# HeadsetR2.net
KiCad netlist of a schematic drawn in EAGLE
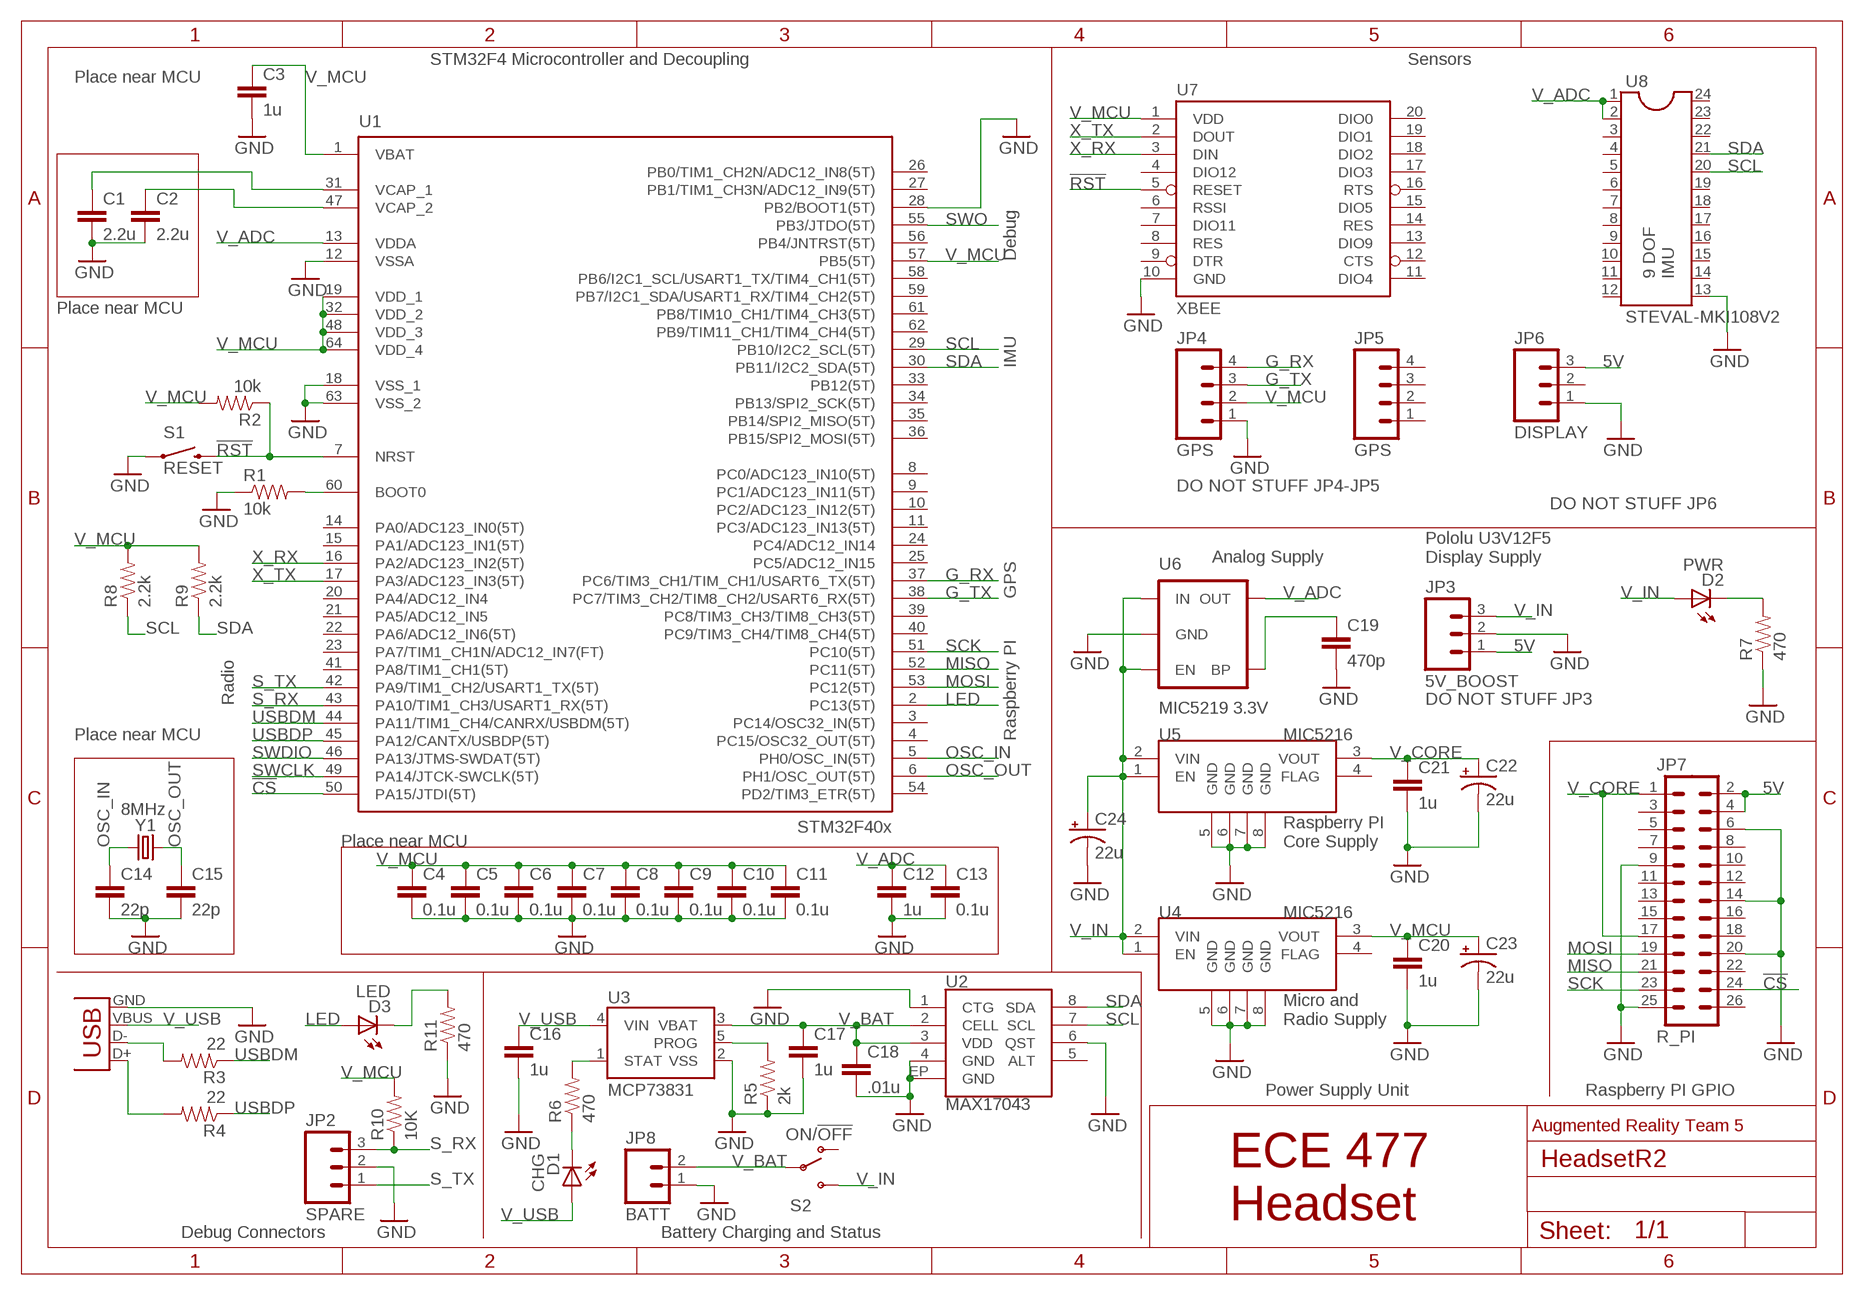
[diagram p0: schematic, sheet 1]

(export (version "E")
  (design (tool "Eeschema 10.0.6"))
  (components
    (comp (ref "C1")
      (value "2.2u")
      (footprint "eagle-import:1206")
      (libsource (lib "eagle-import") (part "CAP1206"))
    )
    (comp (ref "C2")
      (value "2.2u")
      (footprint "eagle-import:1206")
      (libsource (lib "eagle-import") (part "CAP1206"))
    )
    (comp (ref "C3")
      (value "1u")
      (footprint "eagle-import:1206")
      (libsource (lib "eagle-import") (part "CAP1206"))
    )
    (comp (ref "C4")
      (value "0.1u")
      (footprint "eagle-import:1206")
      (libsource (lib "eagle-import") (part "CAP1206"))
    )
    (comp (ref "C5")
      (value "0.1u")
      (footprint "eagle-import:1206")
      (libsource (lib "eagle-import") (part "CAP1206"))
    )
    (comp (ref "C6")
      (value "0.1u")
      (footprint "eagle-import:1206")
      (libsource (lib "eagle-import") (part "CAP1206"))
    )
    (comp (ref "C7")
      (value "0.1u")
      (footprint "eagle-import:1206")
      (libsource (lib "eagle-import") (part "CAP1206"))
    )
    (comp (ref "C8")
      (value "0.1u")
      (footprint "eagle-import:1206")
      (libsource (lib "eagle-import") (part "CAP1206"))
    )
    (comp (ref "C9")
      (value "0.1u")
      (footprint "eagle-import:1206")
      (libsource (lib "eagle-import") (part "CAP1206"))
    )
    (comp (ref "C10")
      (value "0.1u")
      (footprint "eagle-import:1206")
      (libsource (lib "eagle-import") (part "CAP1206"))
    )
    (comp (ref "C11")
      (value "0.1u")
      (footprint "eagle-import:1206")
      (libsource (lib "eagle-import") (part "CAP1206"))
    )
    (comp (ref "C12")
      (value "1u")
      (footprint "eagle-import:1206")
      (libsource (lib "eagle-import") (part "CAP1206"))
    )
    (comp (ref "C13")
      (value "0.1u")
      (footprint "eagle-import:1206")
      (libsource (lib "eagle-import") (part "CAP1206"))
    )
    (comp (ref "C14")
      (value "22p")
      (footprint "eagle-import:1206")
      (libsource (lib "eagle-import") (part "CAP1206"))
    )
    (comp (ref "C15")
      (value "22p")
      (footprint "eagle-import:1206")
      (libsource (lib "eagle-import") (part "CAP1206"))
    )
    (comp (ref "C16")
      (value "1u")
      (footprint "eagle-import:1206")
      (libsource (lib "eagle-import") (part "CAP1206"))
    )
    (comp (ref "C17")
      (value "1u")
      (footprint "eagle-import:1206")
      (libsource (lib "eagle-import") (part "CAP1206"))
    )
    (comp (ref "C18")
      (value ".01u")
      (footprint "eagle-import:1206")
      (libsource (lib "eagle-import") (part "CAP1206"))
    )
    (comp (ref "C19")
      (value "470p")
      (footprint "eagle-import:1206")
      (libsource (lib "eagle-import") (part "CAP1206"))
    )
    (comp (ref "C20")
      (value "1u")
      (footprint "eagle-import:1206")
      (libsource (lib "eagle-import") (part "CAP1206"))
    )
    (comp (ref "C21")
      (value "1u")
      (footprint "eagle-import:1206")
      (libsource (lib "eagle-import") (part "CAP1206"))
    )
    (comp (ref "C22")
      (value "22u")
      (footprint "eagle-import:PANASONIC_D")
      (libsource (lib "eagle-import") (part "CAP_POLD"))
    )
    (comp (ref "C23")
      (value "22u")
      (footprint "eagle-import:PANASONIC_D")
      (libsource (lib "eagle-import") (part "CAP_POLD"))
    )
    (comp (ref "C24")
      (value "22u")
      (footprint "eagle-import:PANASONIC_D")
      (libsource (lib "eagle-import") (part "CAP_POLD"))
    )
    (comp (ref "D1")
      (value "CHG")
      (footprint "eagle-import:LED-1206")
      (libsource (lib "eagle-import") (part "LED-RED1206"))
    )
    (comp (ref "D2")
      (value "PWR")
      (footprint "eagle-import:LED-1206")
      (libsource (lib "eagle-import") (part "LED-RED1206"))
    )
    (comp (ref "D3")
      (value "LED")
      (footprint "eagle-import:LED-1206")
      (libsource (lib "eagle-import") (part "LED-RED1206"))
    )
    (comp (ref "JP1")
      (value "USBSMD")
      (footprint "eagle-import:USB-MINIB")
      (libsource (lib "eagle-import") (part "USBSMD"))
    )
    (comp (ref "JP2")
      (value "SPARE")
      (footprint "eagle-import:1X03")
      (libsource (lib "eagle-import") (part "M03PTH"))
    )
    (comp (ref "JP3")
      (value "5V_BOOST")
      (footprint "eagle-import:1X03")
      (libsource (lib "eagle-import") (part "M03PTH"))
    )
    (comp (ref "JP4")
      (value "GPS")
      (footprint "eagle-import:1X04")
      (libsource (lib "eagle-import") (part "M04PTH"))
    )
    (comp (ref "JP5")
      (value "GPS")
      (footprint "eagle-import:1X04")
      (libsource (lib "eagle-import") (part "M04PTH"))
    )
    (comp (ref "JP6")
      (value "DISPLAY")
      (footprint "eagle-import:1X03")
      (libsource (lib "eagle-import") (part "M03PTH"))
    )
    (comp (ref "JP7")
      (value "R_PI")
      (footprint "eagle-import:2X13")
      (libsource (lib "eagle-import") (part "M13X22X13"))
    )
    (comp (ref "JP8")
      (value "BATT")
      (footprint "eagle-import:JST-2-PTH")
      (libsource (lib "eagle-import") (part "M02JST-PTH-2"))
    )
    (comp (ref "R1")
      (value "10k")
      (footprint "eagle-import:1206")
      (libsource (lib "eagle-import") (part "RES1206"))
    )
    (comp (ref "R2")
      (value "10k")
      (footprint "eagle-import:1206")
      (libsource (lib "eagle-import") (part "RES1206"))
    )
    (comp (ref "R3")
      (value "22")
      (footprint "eagle-import:1206")
      (libsource (lib "eagle-import") (part "RES1206"))
    )
    (comp (ref "R4")
      (value "22")
      (footprint "eagle-import:1206")
      (libsource (lib "eagle-import") (part "RES1206"))
    )
    (comp (ref "R5")
      (value "2k")
      (footprint "eagle-import:1206")
      (libsource (lib "eagle-import") (part "RES1206"))
    )
    (comp (ref "R6")
      (value "470")
      (footprint "eagle-import:1206")
      (libsource (lib "eagle-import") (part "RES1206"))
    )
    (comp (ref "R7")
      (value "470")
      (footprint "eagle-import:1206")
      (libsource (lib "eagle-import") (part "RES1206"))
    )
    (comp (ref "R8")
      (value "2.2k")
      (footprint "eagle-import:1206")
      (libsource (lib "eagle-import") (part "RES1206"))
    )
    (comp (ref "R9")
      (value "2.2k")
      (footprint "eagle-import:1206")
      (libsource (lib "eagle-import") (part "RES1206"))
    )
    (comp (ref "R10")
      (value "10K")
      (footprint "eagle-import:1206")
      (libsource (lib "eagle-import") (part "RES1206"))
    )
    (comp (ref "R11")
      (value "470")
      (footprint "eagle-import:1206")
      (libsource (lib "eagle-import") (part "RES1206"))
    )
    (comp (ref "S1")
      (value "RESET")
      (footprint "eagle-import:TACTILE-PTH")
      (libsource (lib "eagle-import") (part "SWITCH-MOMENTARY-2PTH"))
    )
    (comp (ref "S2")
      (value "ON/!OFF!")
      (footprint "eagle-import:SWITCH-SPDT")
      (libsource (lib "eagle-import") (part "SWITCH-SPDTPTH"))
    )
    (comp (ref "U1")
      (value "STM32F405RGT6")
      (footprint "eagle-import:TQFP64")
      (libsource (lib "eagle-import") (part "STM32F405R"))
    )
    (comp (ref "U2")
      (value "MAX17043")
      (footprint "eagle-import:TDFN-8")
      (libsource (lib "eagle-import") (part "MAX1704X"))
    )
    (comp (ref "U3")
      (value "MCP73831")
      (footprint "eagle-import:SOT23-5")
      (libsource (lib "eagle-import") (part "MCP73831"))
    )
    (comp (ref "U4")
      (value "MIC5216")
      (footprint "eagle-import:MSOP8")
      (libsource (lib "eagle-import") (part "V_REG_MIC5216"))
    )
    (comp (ref "U5")
      (value "MIC5216")
      (footprint "eagle-import:MSOP8")
      (libsource (lib "eagle-import") (part "V_REG_MIC5216"))
    )
    (comp (ref "U6")
      (value "MIC5219 3.3V")
      (footprint "eagle-import:SOT23-5")
      (libsource (lib "eagle-import") (part "V_REG_MIC52193.3V"))
    )
    (comp (ref "U7")
      (value "XBEE")
      (footprint "eagle-import:XBEE-1")
      (libsource (lib "eagle-import") (part "XBEE-1B1"))
    )
    (comp (ref "U8")
      (value "STEVAL-MKI108V2")
      (footprint "eagle-import:DIL24-6")
      (libsource (lib "eagle-import") (part "DIL24-6"))
    )
    (comp (ref "Y1")
      (value "8MHz")
      (footprint "eagle-import:HC49UP")
      (libsource (lib "eagle-import") (part "CRYSTALSMD"))
    )
  )
  (nets
    (net (code "1") (name "/5V") (class "Default")
      (node (ref "JP3") (pin "1") (pinfunction "1_1") (pintype "passive"))
      (node (ref "JP6") (pin "3") (pinfunction "3_3") (pintype "passive"))
      (node (ref "JP7") (pin "2") (pinfunction "2_2") (pintype "passive"))
      (node (ref "JP7") (pin "4") (pinfunction "4_4") (pintype "passive"))
    )
    (net (code "2") (name "/G_RX") (class "Default")
      (node (ref "JP4") (pin "4") (pinfunction "4_4") (pintype "passive"))
      (node (ref "U1") (pin "37") (pinfunction "PC6/TIM3_CH1/TIM_CH1/USART6_TX(5T)_37") (pintype "bidirectional"))
    )
    (net (code "3") (name "/G_TX") (class "Default")
      (node (ref "JP4") (pin "3") (pinfunction "3_3") (pintype "passive"))
      (node (ref "U1") (pin "38") (pinfunction "PC7/TIM3_CH2/TIM8_CH2/USART6_RX(5T)_38") (pintype "bidirectional"))
    )
    (net (code "4") (name "/LED") (class "Default")
      (node (ref "D3") (pin "A") (pinfunction "A_A") (pintype "passive"))
      (node (ref "U1") (pin "2") (pinfunction "PC13(5T)_2") (pintype "bidirectional"))
    )
    (net (code "5") (name "/MISO") (class "Default")
      (node (ref "JP7") (pin "21") (pinfunction "21_21") (pintype "passive"))
      (node (ref "U1") (pin "52") (pinfunction "PC11(5T)_52") (pintype "bidirectional"))
    )
    (net (code "6") (name "/MOSI") (class "Default")
      (node (ref "JP7") (pin "19") (pinfunction "19_19") (pintype "passive"))
      (node (ref "U1") (pin "53") (pinfunction "PC12(5T)_53") (pintype "bidirectional"))
    )
    (net (code "7") (name "/OSC_IN") (class "Default")
      (node (ref "C14") (pin "1") (pinfunction "1_1") (pintype "passive"))
      (node (ref "U1") (pin "5") (pinfunction "PH0/OSC_IN(5T)_5") (pintype "bidirectional"))
      (node (ref "Y1") (pin "1") (pinfunction "1_1") (pintype "passive"))
    )
    (net (code "8") (name "/OSC_OUT") (class "Default")
      (node (ref "C15") (pin "1") (pinfunction "1_1") (pintype "passive"))
      (node (ref "U1") (pin "6") (pinfunction "PH1/OSC_OUT(5T)_6") (pintype "bidirectional"))
      (node (ref "Y1") (pin "2") (pinfunction "2_2") (pintype "passive"))
    )
    (net (code "9") (name "/SCK") (class "Default")
      (node (ref "JP7") (pin "23") (pinfunction "23_23") (pintype "passive"))
      (node (ref "U1") (pin "51") (pinfunction "PC10(5T)_51") (pintype "bidirectional"))
    )
    (net (code "10") (name "/SCL") (class "Default")
      (node (ref "R8") (pin "1") (pinfunction "1_1") (pintype "passive"))
      (node (ref "U1") (pin "29") (pinfunction "PB10/I2C2_SCL(5T)_29") (pintype "bidirectional"))
      (node (ref "U2") (pin "7") (pinfunction "SCL_7") (pintype "bidirectional"))
      (node (ref "U8") (pin "20") (pinfunction "20_20") (pintype "passive"))
    )
    (net (code "11") (name "/SDA") (class "Default")
      (node (ref "R9") (pin "1") (pinfunction "1_1") (pintype "passive"))
      (node (ref "U1") (pin "30") (pinfunction "PB11/I2C2_SDA(5T)_30") (pintype "bidirectional"))
      (node (ref "U2") (pin "8") (pinfunction "SDA_8") (pintype "bidirectional"))
      (node (ref "U8") (pin "21") (pinfunction "21_21") (pintype "passive"))
    )
    (net (code "12") (name "/SWCLK") (class "Default")
      (node (ref "U1") (pin "49") (pinfunction "PA14/JTCK-SWCLK(5T)_49") (pintype "bidirectional"))
    )
    (net (code "13") (name "/SWDIO") (class "Default")
      (node (ref "U1") (pin "46") (pinfunction "PA13/JTMS-SWDAT(5T)_46") (pintype "bidirectional"))
    )
    (net (code "14") (name "/SWO") (class "Default")
      (node (ref "U1") (pin "55") (pinfunction "PB3/JTDO(5T)_55") (pintype "bidirectional"))
    )
    (net (code "15") (name "/S_RX") (class "Default")
      (node (ref "JP2") (pin "3") (pinfunction "3_3") (pintype "passive"))
      (node (ref "R10") (pin "1") (pinfunction "1_1") (pintype "passive"))
      (node (ref "U1") (pin "43") (pinfunction "PA10/TIM1_CH3/USART1_RX(5T)_43") (pintype "bidirectional"))
    )
    (net (code "16") (name "/S_TX") (class "Default")
      (node (ref "JP2") (pin "1") (pinfunction "1_1") (pintype "passive"))
      (node (ref "U1") (pin "42") (pinfunction "PA9/TIM1_CH2/USART1_TX(5T)_42") (pintype "bidirectional"))
    )
    (net (code "17") (name "/USBDM") (class "Default")
      (node (ref "R3") (pin "1") (pinfunction "1_1") (pintype "passive"))
      (node (ref "U1") (pin "44") (pinfunction "PA11/TIM1_CH4/CANRX/USBDM(5T)_44") (pintype "bidirectional"))
    )
    (net (code "18") (name "/USBDP") (class "Default")
      (node (ref "R4") (pin "1") (pinfunction "1_1") (pintype "passive"))
      (node (ref "U1") (pin "45") (pinfunction "PA12/CANTX/USBDP(5T)_45") (pintype "bidirectional"))
    )
    (net (code "19") (name "/V_ADC") (class "Default")
      (node (ref "C12") (pin "1") (pinfunction "1_1") (pintype "passive"))
      (node (ref "C13") (pin "1") (pinfunction "1_1") (pintype "passive"))
      (node (ref "U1") (pin "13") (pinfunction "VDDA_13") (pintype "bidirectional"))
      (node (ref "U6") (pin "5") (pinfunction "OUT_5") (pintype "passive"))
      (node (ref "U8") (pin "1") (pinfunction "1_1") (pintype "passive"))
      (node (ref "U8") (pin "2") (pinfunction "2_2") (pintype "passive"))
    )
    (net (code "20") (name "/V_BAT") (class "Default")
      (node (ref "C17") (pin "1") (pinfunction "1_1") (pintype "passive"))
      (node (ref "C18") (pin "1") (pinfunction "1_1") (pintype "passive"))
      (node (ref "JP8") (pin "2") (pinfunction "2_2") (pintype "passive"))
      (node (ref "S2") (pin "2") (pinfunction "P_2") (pintype "passive"))
      (node (ref "U2") (pin "2") (pinfunction "CELL_2") (pintype "bidirectional"))
      (node (ref "U2") (pin "3") (pinfunction "VDD_3") (pintype "bidirectional"))
      (node (ref "U3") (pin "3") (pinfunction "VBAT_3") (pintype "power_in"))
    )
    (net (code "21") (name "/V_CORE") (class "Default")
      (node (ref "C21") (pin "1") (pinfunction "1_1") (pintype "passive"))
      (node (ref "C22") (pin "+") (pinfunction "+_+") (pintype "passive"))
      (node (ref "JP7") (pin "1") (pinfunction "1_1") (pintype "passive"))
      (node (ref "JP7") (pin "17") (pinfunction "17_17") (pintype "passive"))
      (node (ref "U5") (pin "3") (pinfunction "VOUT_3") (pintype "bidirectional"))
    )
    (net (code "22") (name "/V_IN") (class "Default")
      (node (ref "C24") (pin "+") (pinfunction "+_+") (pintype "passive"))
      (node (ref "D2") (pin "A") (pinfunction "A_A") (pintype "passive"))
      (node (ref "JP3") (pin "3") (pinfunction "3_3") (pintype "passive"))
      (node (ref "S2") (pin "3") (pinfunction "S_3") (pintype "passive"))
      (node (ref "U4") (pin "1") (pinfunction "EN_1") (pintype "bidirectional"))
      (node (ref "U4") (pin "2") (pinfunction "VIN_2") (pintype "bidirectional"))
      (node (ref "U5") (pin "1") (pinfunction "EN_1") (pintype "bidirectional"))
      (node (ref "U5") (pin "2") (pinfunction "VIN_2") (pintype "bidirectional"))
      (node (ref "U6") (pin "1") (pinfunction "IN_1") (pintype "input"))
      (node (ref "U6") (pin "3") (pinfunction "EN_3") (pintype "input"))
    )
    (net (code "23") (name "/V_MCU") (class "Default")
      (node (ref "C10") (pin "1") (pinfunction "1_1") (pintype "passive"))
      (node (ref "C11") (pin "1") (pinfunction "1_1") (pintype "passive"))
      (node (ref "C20") (pin "1") (pinfunction "1_1") (pintype "passive"))
      (node (ref "C23") (pin "+") (pinfunction "+_+") (pintype "passive"))
      (node (ref "C3") (pin "1") (pinfunction "1_1") (pintype "passive"))
      (node (ref "C4") (pin "1") (pinfunction "1_1") (pintype "passive"))
      (node (ref "C5") (pin "1") (pinfunction "1_1") (pintype "passive"))
      (node (ref "C6") (pin "1") (pinfunction "1_1") (pintype "passive"))
      (node (ref "C7") (pin "1") (pinfunction "1_1") (pintype "passive"))
      (node (ref "C8") (pin "1") (pinfunction "1_1") (pintype "passive"))
      (node (ref "C9") (pin "1") (pinfunction "1_1") (pintype "passive"))
      (node (ref "JP4") (pin "2") (pinfunction "2_2") (pintype "passive"))
      (node (ref "R10") (pin "2") (pinfunction "2_2") (pintype "passive"))
      (node (ref "R2") (pin "2") (pinfunction "2_2") (pintype "passive"))
      (node (ref "R8") (pin "2") (pinfunction "2_2") (pintype "passive"))
      (node (ref "R9") (pin "2") (pinfunction "2_2") (pintype "passive"))
      (node (ref "U1") (pin "1") (pinfunction "VBAT_1") (pintype "bidirectional"))
      (node (ref "U1") (pin "19") (pinfunction "VDD_1_19") (pintype "bidirectional"))
      (node (ref "U1") (pin "32") (pinfunction "VDD_2_32") (pintype "bidirectional"))
      (node (ref "U1") (pin "48") (pinfunction "VDD_3_48") (pintype "bidirectional"))
      (node (ref "U1") (pin "57") (pinfunction "PB5(5T)_57") (pintype "bidirectional"))
      (node (ref "U1") (pin "64") (pinfunction "VDD_4_64") (pintype "bidirectional"))
      (node (ref "U4") (pin "3") (pinfunction "VOUT_3") (pintype "bidirectional"))
      (node (ref "U7") (pin "1") (pinfunction "VDD_1") (pintype "power_in"))
    )
    (net (code "24") (name "/V_USB") (class "Default")
      (node (ref "C16") (pin "1") (pinfunction "1_1") (pintype "passive"))
      (node (ref "D1") (pin "A") (pinfunction "A_A") (pintype "passive"))
      (node (ref "JP1") (pin "VBUS") (pinfunction "VBUS_VBUS") (pintype "bidirectional"))
      (node (ref "U3") (pin "4") (pinfunction "VIN_4") (pintype "power_in"))
    )
    (net (code "25") (name "/X_RX") (class "Default")
      (node (ref "U1") (pin "16") (pinfunction "PA2/ADC123_IN2(5T)_16") (pintype "bidirectional"))
      (node (ref "U7") (pin "3") (pinfunction "DIN_3") (pintype "input"))
    )
    (net (code "26") (name "/X_TX") (class "Default")
      (node (ref "U1") (pin "17") (pinfunction "PA3/ADC123_IN3(5T)_17") (pintype "bidirectional"))
      (node (ref "U7") (pin "2") (pinfunction "DOUT_2") (pintype "output"))
    )
    (net (code "27") (name "/~{CS}") (class "Default")
      (node (ref "JP7") (pin "24") (pinfunction "24_24") (pintype "passive"))
      (node (ref "U1") (pin "50") (pinfunction "PA15/JTDI(5T)_50") (pintype "bidirectional"))
    )
    (net (code "28") (name "/~{RST}") (class "Default")
      (node (ref "R2") (pin "1") (pinfunction "1_1") (pintype "passive"))
      (node (ref "S1") (pin "3") (pinfunction "2_3") (pintype "passive"))
      (node (ref "U1") (pin "7") (pinfunction "NRST_7") (pintype "bidirectional"))
      (node (ref "U7") (pin "5") (pinfunction "RESET_5") (pintype "input"))
    )
    (net (code "29") (name "GND") (class "Default")
      (node (ref "C1") (pin "2") (pinfunction "2_2") (pintype "passive"))
      (node (ref "C10") (pin "2") (pinfunction "2_2") (pintype "passive"))
      (node (ref "C11") (pin "2") (pinfunction "2_2") (pintype "passive"))
      (node (ref "C12") (pin "2") (pinfunction "2_2") (pintype "passive"))
      (node (ref "C13") (pin "2") (pinfunction "2_2") (pintype "passive"))
      (node (ref "C14") (pin "2") (pinfunction "2_2") (pintype "passive"))
      (node (ref "C15") (pin "2") (pinfunction "2_2") (pintype "passive"))
      (node (ref "C16") (pin "2") (pinfunction "2_2") (pintype "passive"))
      (node (ref "C17") (pin "2") (pinfunction "2_2") (pintype "passive"))
      (node (ref "C18") (pin "2") (pinfunction "2_2") (pintype "passive"))
      (node (ref "C19") (pin "2") (pinfunction "2_2") (pintype "passive"))
      (node (ref "C2") (pin "2") (pinfunction "2_2") (pintype "passive"))
      (node (ref "C20") (pin "2") (pinfunction "2_2") (pintype "passive"))
      (node (ref "C21") (pin "2") (pinfunction "2_2") (pintype "passive"))
      (node (ref "C22") (pin "-") (pinfunction "-_-") (pintype "passive"))
      (node (ref "C23") (pin "-") (pinfunction "-_-") (pintype "passive"))
      (node (ref "C24") (pin "-") (pinfunction "-_-") (pintype "passive"))
      (node (ref "C3") (pin "2") (pinfunction "2_2") (pintype "passive"))
      (node (ref "C4") (pin "2") (pinfunction "2_2") (pintype "passive"))
      (node (ref "C5") (pin "2") (pinfunction "2_2") (pintype "passive"))
      (node (ref "C6") (pin "2") (pinfunction "2_2") (pintype "passive"))
      (node (ref "C7") (pin "2") (pinfunction "2_2") (pintype "passive"))
      (node (ref "C8") (pin "2") (pinfunction "2_2") (pintype "passive"))
      (node (ref "C9") (pin "2") (pinfunction "2_2") (pintype "passive"))
      (node (ref "JP1") (pin "GND") (pinfunction "GND_GND") (pintype "bidirectional"))
      (node (ref "JP2") (pin "2") (pinfunction "2_2") (pintype "passive"))
      (node (ref "JP3") (pin "2") (pinfunction "2_2") (pintype "passive"))
      (node (ref "JP4") (pin "1") (pinfunction "1_1") (pintype "passive"))
      (node (ref "JP6") (pin "1") (pinfunction "1_1") (pintype "passive"))
      (node (ref "JP7") (pin "14") (pinfunction "14_14") (pintype "passive"))
      (node (ref "JP7") (pin "20") (pinfunction "20_20") (pintype "passive"))
      (node (ref "JP7") (pin "25") (pinfunction "25_25") (pintype "passive"))
      (node (ref "JP7") (pin "6") (pinfunction "6_6") (pintype "passive"))
      (node (ref "JP7") (pin "9") (pinfunction "9_9") (pintype "passive"))
      (node (ref "JP8") (pin "1") (pinfunction "1_1") (pintype "passive"))
      (node (ref "R1") (pin "1") (pinfunction "1_1") (pintype "passive"))
      (node (ref "R11") (pin "1") (pinfunction "1_1") (pintype "passive"))
      (node (ref "R5") (pin "1") (pinfunction "1_1") (pintype "passive"))
      (node (ref "R7") (pin "1") (pinfunction "1_1") (pintype "passive"))
      (node (ref "S1") (pin "1") (pinfunction "1_1") (pintype "passive"))
      (node (ref "U1") (pin "12") (pinfunction "VSSA_12") (pintype "bidirectional"))
      (node (ref "U1") (pin "18") (pinfunction "VSS_1_18") (pintype "bidirectional"))
      (node (ref "U1") (pin "28") (pinfunction "PB2/BOOT1(5T)_28") (pintype "bidirectional"))
      (node (ref "U1") (pin "63") (pinfunction "VSS_2_63") (pintype "bidirectional"))
      (node (ref "U2") (pin "1") (pinfunction "CTG_1") (pintype "bidirectional"))
      (node (ref "U2") (pin "4") (pinfunction "GND_4") (pintype "bidirectional"))
      (node (ref "U2") (pin "6") (pinfunction "QST_6") (pintype "bidirectional"))
      (node (ref "U2") (pin "EP") (pinfunction "GND_EP") (pintype "bidirectional"))
      (node (ref "U3") (pin "2") (pinfunction "VSS_2") (pintype "power_in"))
      (node (ref "U4") (pin "5") (pinfunction "GND_5") (pintype "bidirectional"))
      (node (ref "U4") (pin "6") (pinfunction "GND_6") (pintype "bidirectional"))
      (node (ref "U4") (pin "7") (pinfunction "GND_7") (pintype "bidirectional"))
      (node (ref "U4") (pin "8") (pinfunction "GND_8") (pintype "bidirectional"))
      (node (ref "U5") (pin "5") (pinfunction "GND_5") (pintype "bidirectional"))
      (node (ref "U5") (pin "6") (pinfunction "GND_6") (pintype "bidirectional"))
      (node (ref "U5") (pin "7") (pinfunction "GND_7") (pintype "bidirectional"))
      (node (ref "U5") (pin "8") (pinfunction "GND_8") (pintype "bidirectional"))
      (node (ref "U6") (pin "2") (pinfunction "GND_2") (pintype "input"))
      (node (ref "U7") (pin "10") (pinfunction "GND_10") (pintype "power_in"))
      (node (ref "U8") (pin "13") (pinfunction "13_13") (pintype "passive"))
    )
    (net (code "30") (name "Net-(D1-PadC)") (class "Default")
      (node (ref "D1") (pin "C") (pinfunction "C_C") (pintype "passive"))
      (node (ref "R6") (pin "1") (pinfunction "1_1") (pintype "passive"))
    )
    (net (code "31") (name "Net-(D2-PadC)") (class "Default")
      (node (ref "D2") (pin "C") (pinfunction "C_C") (pintype "passive"))
      (node (ref "R7") (pin "2") (pinfunction "2_2") (pintype "passive"))
    )
    (net (code "32") (name "Net-(D3-PadC)") (class "Default")
      (node (ref "D3") (pin "C") (pinfunction "C_C") (pintype "passive"))
      (node (ref "R11") (pin "2") (pinfunction "2_2") (pintype "passive"))
    )
    (net (code "33") (name "Net-(JP1-PadD+)") (class "Default")
      (node (ref "JP1") (pin "D+") (pinfunction "D+_D+") (pintype "bidirectional"))
      (node (ref "R4") (pin "2") (pinfunction "2_2") (pintype "passive"))
    )
    (net (code "34") (name "Net-(JP1-PadD-)") (class "Default")
      (node (ref "JP1") (pin "D-") (pinfunction "D-_D-") (pintype "bidirectional"))
      (node (ref "R3") (pin "2") (pinfunction "2_2") (pintype "passive"))
    )
    (net (code "35") (name "Net-(U1-BOOT0)") (class "Default")
      (node (ref "R1") (pin "2") (pinfunction "2_2") (pintype "passive"))
      (node (ref "U1") (pin "60") (pinfunction "BOOT0_60") (pintype "bidirectional"))
    )
    (net (code "36") (name "Net-(U1-VCAP_1)") (class "Default")
      (node (ref "C1") (pin "1") (pinfunction "1_1") (pintype "passive"))
      (node (ref "U1") (pin "31") (pinfunction "VCAP_1_31") (pintype "bidirectional"))
    )
    (net (code "37") (name "Net-(U1-VCAP_2)") (class "Default")
      (node (ref "C2") (pin "1") (pinfunction "1_1") (pintype "passive"))
      (node (ref "U1") (pin "47") (pinfunction "VCAP_2_47") (pintype "bidirectional"))
    )
    (net (code "38") (name "Net-(U3-PROG)") (class "Default")
      (node (ref "R5") (pin "2") (pinfunction "2_2") (pintype "passive"))
      (node (ref "U3") (pin "5") (pinfunction "PROG_5") (pintype "input"))
    )
    (net (code "39") (name "Net-(U3-STAT)") (class "Default")
      (node (ref "R6") (pin "2") (pinfunction "2_2") (pintype "passive"))
      (node (ref "U3") (pin "1") (pinfunction "STAT_1") (pintype "output"))
    )
    (net (code "40") (name "Net-(U6-BP)") (class "Default")
      (node (ref "C19") (pin "1") (pinfunction "1_1") (pintype "passive"))
      (node (ref "U6") (pin "4") (pinfunction "BP_4") (pintype "input"))
    )
    (net (code "41") (name "unconnected-(JP5-Pad1)") (class "Default")
      (node (ref "JP5") (pin "1") (pinfunction "1_1") (pintype "passive"))
    )
    (net (code "42") (name "unconnected-(JP5-Pad2)") (class "Default")
      (node (ref "JP5") (pin "2") (pinfunction "2_2") (pintype "passive"))
    )
    (net (code "43") (name "unconnected-(JP5-Pad3)") (class "Default")
      (node (ref "JP5") (pin "3") (pinfunction "3_3") (pintype "passive"))
    )
    (net (code "44") (name "unconnected-(JP5-Pad4)") (class "Default")
      (node (ref "JP5") (pin "4") (pinfunction "4_4") (pintype "passive"))
    )
    (net (code "45") (name "unconnected-(JP6-Pad2)") (class "Default")
      (node (ref "JP6") (pin "2") (pinfunction "2_2") (pintype "passive"))
    )
    (net (code "46") (name "unconnected-(JP7-Pad3)") (class "Default")
      (node (ref "JP7") (pin "3") (pinfunction "3_3") (pintype "passive"))
    )
    (net (code "47") (name "unconnected-(JP7-Pad5)") (class "Default")
      (node (ref "JP7") (pin "5") (pinfunction "5_5") (pintype "passive"))
    )
    (net (code "48") (name "unconnected-(JP7-Pad7)") (class "Default")
      (node (ref "JP7") (pin "7") (pinfunction "7_7") (pintype "passive"))
    )
    (net (code "49") (name "unconnected-(JP7-Pad8)") (class "Default")
      (node (ref "JP7") (pin "8") (pinfunction "8_8") (pintype "passive"))
    )
    (net (code "50") (name "unconnected-(JP7-Pad10)") (class "Default")
      (node (ref "JP7") (pin "10") (pinfunction "10_10") (pintype "passive"))
    )
    (net (code "51") (name "unconnected-(JP7-Pad11)") (class "Default")
      (node (ref "JP7") (pin "11") (pinfunction "11_11") (pintype "passive"))
    )
    (net (code "52") (name "unconnected-(JP7-Pad12)") (class "Default")
      (node (ref "JP7") (pin "12") (pinfunction "12_12") (pintype "passive"))
    )
    (net (code "53") (name "unconnected-(JP7-Pad13)") (class "Default")
      (node (ref "JP7") (pin "13") (pinfunction "13_13") (pintype "passive"))
    )
    (net (code "54") (name "unconnected-(JP7-Pad15)") (class "Default")
      (node (ref "JP7") (pin "15") (pinfunction "15_15") (pintype "passive"))
    )
    (net (code "55") (name "unconnected-(JP7-Pad16)") (class "Default")
      (node (ref "JP7") (pin "16") (pinfunction "16_16") (pintype "passive"))
    )
    (net (code "56") (name "unconnected-(JP7-Pad18)") (class "Default")
      (node (ref "JP7") (pin "18") (pinfunction "18_18") (pintype "passive"))
    )
    (net (code "57") (name "unconnected-(JP7-Pad22)") (class "Default")
      (node (ref "JP7") (pin "22") (pinfunction "22_22") (pintype "passive"))
    )
    (net (code "58") (name "unconnected-(JP7-Pad26)") (class "Default")
      (node (ref "JP7") (pin "26") (pinfunction "26_26") (pintype "passive"))
    )
    (net (code "59") (name "unconnected-(S2-O-Pad1)") (class "Default")
      (node (ref "S2") (pin "1") (pinfunction "O_1") (pintype "passive"))
    )
    (net (code "60") (name "unconnected-(U1-PA0{slash}ADC123_IN0(5T)-Pad14)") (class "Default")
      (node (ref "U1") (pin "14") (pinfunction "PA0/ADC123_IN0(5T)_14") (pintype "bidirectional"))
    )
    (net (code "61") (name "unconnected-(U1-PA1{slash}ADC123_IN1(5T)-Pad15)") (class "Default")
      (node (ref "U1") (pin "15") (pinfunction "PA1/ADC123_IN1(5T)_15") (pintype "bidirectional"))
    )
    (net (code "62") (name "unconnected-(U1-PA4{slash}ADC12_IN4-Pad20)") (class "Default")
      (node (ref "U1") (pin "20") (pinfunction "PA4/ADC12_IN4_20") (pintype "bidirectional"))
    )
    (net (code "63") (name "unconnected-(U1-PA5{slash}ADC12_IN5-Pad21)") (class "Default")
      (node (ref "U1") (pin "21") (pinfunction "PA5/ADC12_IN5_21") (pintype "bidirectional"))
    )
    (net (code "64") (name "unconnected-(U1-PA6{slash}ADC12_IN6(5T)-Pad22)") (class "Default")
      (node (ref "U1") (pin "22") (pinfunction "PA6/ADC12_IN6(5T)_22") (pintype "bidirectional"))
    )
    (net (code "65") (name "unconnected-(U1-PA7{slash}TIM1_CH1N{slash}ADC12_IN7(FT)-Pad23)") (class "Default")
      (node (ref "U1") (pin "23") (pinfunction "PA7/TIM1_CH1N/ADC12_IN7(FT)_23") (pintype "bidirectional"))
    )
    (net (code "66") (name "unconnected-(U1-PA8{slash}TIM1_CH1(5T)-Pad41)") (class "Default")
      (node (ref "U1") (pin "41") (pinfunction "PA8/TIM1_CH1(5T)_41") (pintype "bidirectional"))
    )
    (net (code "67") (name "unconnected-(U1-PB0{slash}TIM1_CH2N{slash}ADC12_IN8(5T)-Pad26)") (class "Default")
      (node (ref "U1") (pin "26") (pinfunction "PB0/TIM1_CH2N/ADC12_IN8(5T)_26") (pintype "bidirectional"))
    )
    (net (code "68") (name "unconnected-(U1-PB1{slash}TIM1_CH3N{slash}ADC12_IN9(5T)-Pad27)") (class "Default")
      (node (ref "U1") (pin "27") (pinfunction "PB1/TIM1_CH3N/ADC12_IN9(5T)_27") (pintype "bidirectional"))
    )
    (net (code "69") (name "unconnected-(U1-PB4{slash}JNTRST(5T)-Pad56)") (class "Default")
      (node (ref "U1") (pin "56") (pinfunction "PB4/JNTRST(5T)_56") (pintype "bidirectional"))
    )
    (net (code "70") (name "unconnected-(U1-PB6{slash}I2C1_SCL{slash}USART1_TX{slash}TIM4_CH1(5T)-Pad58)") (class "Default")
      (node (ref "U1") (pin "58") (pinfunction "PB6/I2C1_SCL/USART1_TX/TIM4_CH1(5T)_58") (pintype "bidirectional"))
    )
    (net (code "71") (name "unconnected-(U1-PB7{slash}I2C1_SDA{slash}USART1_RX{slash}TIM4_CH2(5T)-Pad59)") (class "Default")
      (node (ref "U1") (pin "59") (pinfunction "PB7/I2C1_SDA/USART1_RX/TIM4_CH2(5T)_59") (pintype "bidirectional"))
    )
    (net (code "72") (name "unconnected-(U1-PB8{slash}TIM10_CH1{slash}TIM4_CH3(5T)-Pad61)") (class "Default")
      (node (ref "U1") (pin "61") (pinfunction "PB8/TIM10_CH1/TIM4_CH3(5T)_61") (pintype "bidirectional"))
    )
    (net (code "73") (name "unconnected-(U1-PB9{slash}TIM11_CH1{slash}TIM4_CH4(5T)-Pad62)") (class "Default")
      (node (ref "U1") (pin "62") (pinfunction "PB9/TIM11_CH1/TIM4_CH4(5T)_62") (pintype "bidirectional"))
    )
    (net (code "74") (name "unconnected-(U1-PB12(5T)-Pad33)") (class "Default")
      (node (ref "U1") (pin "33") (pinfunction "PB12(5T)_33") (pintype "bidirectional"))
    )
    (net (code "75") (name "unconnected-(U1-PB13{slash}SPI2_SCK(5T)-Pad34)") (class "Default")
      (node (ref "U1") (pin "34") (pinfunction "PB13/SPI2_SCK(5T)_34") (pintype "bidirectional"))
    )
    (net (code "76") (name "unconnected-(U1-PB14{slash}SPI2_MISO(5T)-Pad35)") (class "Default")
      (node (ref "U1") (pin "35") (pinfunction "PB14/SPI2_MISO(5T)_35") (pintype "bidirectional"))
    )
    (net (code "77") (name "unconnected-(U1-PB15{slash}SPI2_MOSI(5T)-Pad36)") (class "Default")
      (node (ref "U1") (pin "36") (pinfunction "PB15/SPI2_MOSI(5T)_36") (pintype "bidirectional"))
    )
    (net (code "78") (name "unconnected-(U1-PC0{slash}ADC123_IN10(5T)-Pad8)") (class "Default")
      (node (ref "U1") (pin "8") (pinfunction "PC0/ADC123_IN10(5T)_8") (pintype "bidirectional"))
    )
    (net (code "79") (name "unconnected-(U1-PC1{slash}ADC123_IN11(5T)-Pad9)") (class "Default")
      (node (ref "U1") (pin "9") (pinfunction "PC1/ADC123_IN11(5T)_9") (pintype "bidirectional"))
    )
    (net (code "80") (name "unconnected-(U1-PC2{slash}ADC123_IN12(5T)-Pad10)") (class "Default")
      (node (ref "U1") (pin "10") (pinfunction "PC2/ADC123_IN12(5T)_10") (pintype "bidirectional"))
    )
    (net (code "81") (name "unconnected-(U1-PC3{slash}ADC123_IN13(5T)-Pad11)") (class "Default")
      (node (ref "U1") (pin "11") (pinfunction "PC3/ADC123_IN13(5T)_11") (pintype "bidirectional"))
    )
    (net (code "82") (name "unconnected-(U1-PC4{slash}ADC12_IN14-Pad24)") (class "Default")
      (node (ref "U1") (pin "24") (pinfunction "PC4/ADC12_IN14_24") (pintype "bidirectional"))
    )
    (net (code "83") (name "unconnected-(U1-PC5{slash}ADC12_IN15-Pad25)") (class "Default")
      (node (ref "U1") (pin "25") (pinfunction "PC5/ADC12_IN15_25") (pintype "bidirectional"))
    )
    (net (code "84") (name "unconnected-(U1-PC8{slash}TIM3_CH3{slash}TIM8_CH3(5T)-Pad39)") (class "Default")
      (node (ref "U1") (pin "39") (pinfunction "PC8/TIM3_CH3/TIM8_CH3(5T)_39") (pintype "bidirectional"))
    )
    (net (code "85") (name "unconnected-(U1-PC9{slash}TIM3_CH4{slash}TIM8_CH4(5T)-Pad40)") (class "Default")
      (node (ref "U1") (pin "40") (pinfunction "PC9/TIM3_CH4/TIM8_CH4(5T)_40") (pintype "bidirectional"))
    )
    (net (code "86") (name "unconnected-(U1-PC14{slash}OSC32_IN(5T)-Pad3)") (class "Default")
      (node (ref "U1") (pin "3") (pinfunction "PC14/OSC32_IN(5T)_3") (pintype "bidirectional"))
    )
    (net (code "87") (name "unconnected-(U1-PC15{slash}OSC32_OUT(5T)-Pad4)") (class "Default")
      (node (ref "U1") (pin "4") (pinfunction "PC15/OSC32_OUT(5T)_4") (pintype "bidirectional"))
    )
    (net (code "88") (name "unconnected-(U1-PD2{slash}TIM3_ETR(5T)-Pad54)") (class "Default")
      (node (ref "U1") (pin "54") (pinfunction "PD2/TIM3_ETR(5T)_54") (pintype "bidirectional"))
    )
    (net (code "89") (name "unconnected-(U2-ALT-Pad5)") (class "Default")
      (node (ref "U2") (pin "5") (pinfunction "ALT_5") (pintype "bidirectional"))
    )
    (net (code "90") (name "unconnected-(U4-FLAG-Pad4)") (class "Default")
      (node (ref "U4") (pin "4") (pinfunction "FLAG_4") (pintype "bidirectional"))
    )
    (net (code "91") (name "unconnected-(U5-FLAG-Pad4)") (class "Default")
      (node (ref "U5") (pin "4") (pinfunction "FLAG_4") (pintype "bidirectional"))
    )
    (net (code "92") (name "unconnected-(U7-CTS-Pad12)") (class "Default")
      (node (ref "U7") (pin "12") (pinfunction "CTS_12") (pintype "output"))
    )
    (net (code "93") (name "unconnected-(U7-DIO0-Pad20)") (class "Default")
      (node (ref "U7") (pin "20") (pinfunction "DIO0_20") (pintype "bidirectional"))
    )
    (net (code "94") (name "unconnected-(U7-DIO1-Pad19)") (class "Default")
      (node (ref "U7") (pin "19") (pinfunction "DIO1_19") (pintype "bidirectional"))
    )
    (net (code "95") (name "unconnected-(U7-DIO2-Pad18)") (class "Default")
      (node (ref "U7") (pin "18") (pinfunction "DIO2_18") (pintype "bidirectional"))
    )
    (net (code "96") (name "unconnected-(U7-DIO3-Pad17)") (class "Default")
      (node (ref "U7") (pin "17") (pinfunction "DIO3_17") (pintype "bidirectional"))
    )
    (net (code "97") (name "unconnected-(U7-DIO4-Pad11)") (class "Default")
      (node (ref "U7") (pin "11") (pinfunction "DIO4_11") (pintype "bidirectional"))
    )
    (net (code "98") (name "unconnected-(U7-DIO5-Pad15)") (class "Default")
      (node (ref "U7") (pin "15") (pinfunction "DIO5_15") (pintype "bidirectional"))
    )
    (net (code "99") (name "unconnected-(U7-DIO9-Pad13)") (class "Default")
      (node (ref "U7") (pin "13") (pinfunction "DIO9_13") (pintype "bidirectional"))
    )
    (net (code "100") (name "unconnected-(U7-DIO11-Pad7)") (class "Default")
      (node (ref "U7") (pin "7") (pinfunction "DIO11_7") (pintype "bidirectional"))
    )
    (net (code "101") (name "unconnected-(U7-DIO12-Pad4)") (class "Default")
      (node (ref "U7") (pin "4") (pinfunction "DIO12_4") (pintype "bidirectional"))
    )
    (net (code "102") (name "unconnected-(U7-DTR-Pad9)") (class "Default")
      (node (ref "U7") (pin "9") (pinfunction "DTR_9") (pintype "bidirectional"))
    )
    (net (code "103") (name "unconnected-(U7-RES-Pad8)") (class "Default")
      (node (ref "U7") (pin "8") (pinfunction "RES_8") (pintype "bidirectional"))
    )
    (net (code "104") (name "unconnected-(U7-RES-Pad14)") (class "Default")
      (node (ref "U7") (pin "14") (pinfunction "RES_14") (pintype "bidirectional"))
    )
    (net (code "105") (name "unconnected-(U7-RSSI-Pad6)") (class "Default")
      (node (ref "U7") (pin "6") (pinfunction "RSSI_6") (pintype "bidirectional"))
    )
    (net (code "106") (name "unconnected-(U7-RTS-Pad16)") (class "Default")
      (node (ref "U7") (pin "16") (pinfunction "RTS_16") (pintype "input"))
    )
    (net (code "107") (name "unconnected-(U8-Pad3)") (class "Default")
      (node (ref "U8") (pin "3") (pinfunction "3_3") (pintype "passive"))
    )
    (net (code "108") (name "unconnected-(U8-Pad4)") (class "Default")
      (node (ref "U8") (pin "4") (pinfunction "4_4") (pintype "passive"))
    )
    (net (code "109") (name "unconnected-(U8-Pad5)") (class "Default")
      (node (ref "U8") (pin "5") (pinfunction "5_5") (pintype "passive"))
    )
    (net (code "110") (name "unconnected-(U8-Pad6)") (class "Default")
      (node (ref "U8") (pin "6") (pinfunction "6_6") (pintype "passive"))
    )
    (net (code "111") (name "unconnected-(U8-Pad7)") (class "Default")
      (node (ref "U8") (pin "7") (pinfunction "7_7") (pintype "passive"))
    )
    (net (code "112") (name "unconnected-(U8-Pad8)") (class "Default")
      (node (ref "U8") (pin "8") (pinfunction "8_8") (pintype "passive"))
    )
    (net (code "113") (name "unconnected-(U8-Pad9)") (class "Default")
      (node (ref "U8") (pin "9") (pinfunction "9_9") (pintype "passive"))
    )
    (net (code "114") (name "unconnected-(U8-Pad10)") (class "Default")
      (node (ref "U8") (pin "10") (pinfunction "10_10") (pintype "passive"))
    )
    (net (code "115") (name "unconnected-(U8-Pad11)") (class "Default")
      (node (ref "U8") (pin "11") (pinfunction "11_11") (pintype "passive"))
    )
    (net (code "116") (name "unconnected-(U8-Pad12)") (class "Default")
      (node (ref "U8") (pin "12") (pinfunction "12_12") (pintype "passive"))
    )
    (net (code "117") (name "unconnected-(U8-Pad14)") (class "Default")
      (node (ref "U8") (pin "14") (pinfunction "14_14") (pintype "passive"))
    )
    (net (code "118") (name "unconnected-(U8-Pad15)") (class "Default")
      (node (ref "U8") (pin "15") (pinfunction "15_15") (pintype "passive"))
    )
    (net (code "119") (name "unconnected-(U8-Pad16)") (class "Default")
      (node (ref "U8") (pin "16") (pinfunction "16_16") (pintype "passive"))
    )
    (net (code "120") (name "unconnected-(U8-Pad17)") (class "Default")
      (node (ref "U8") (pin "17") (pinfunction "17_17") (pintype "passive"))
    )
    (net (code "121") (name "unconnected-(U8-Pad18)") (class "Default")
      (node (ref "U8") (pin "18") (pinfunction "18_18") (pintype "passive"))
    )
    (net (code "122") (name "unconnected-(U8-Pad19)") (class "Default")
      (node (ref "U8") (pin "19") (pinfunction "19_19") (pintype "passive"))
    )
    (net (code "123") (name "unconnected-(U8-Pad22)") (class "Default")
      (node (ref "U8") (pin "22") (pinfunction "22_22") (pintype "passive"))
    )
    (net (code "124") (name "unconnected-(U8-Pad23)") (class "Default")
      (node (ref "U8") (pin "23") (pinfunction "23_23") (pintype "passive"))
    )
    (net (code "125") (name "unconnected-(U8-Pad24)") (class "Default")
      (node (ref "U8") (pin "24") (pinfunction "24_24") (pintype "passive"))
    )
  )
)
